# Ganganzeige_nutzen.net
KiCad netlist of a schematic drawn in EAGLE
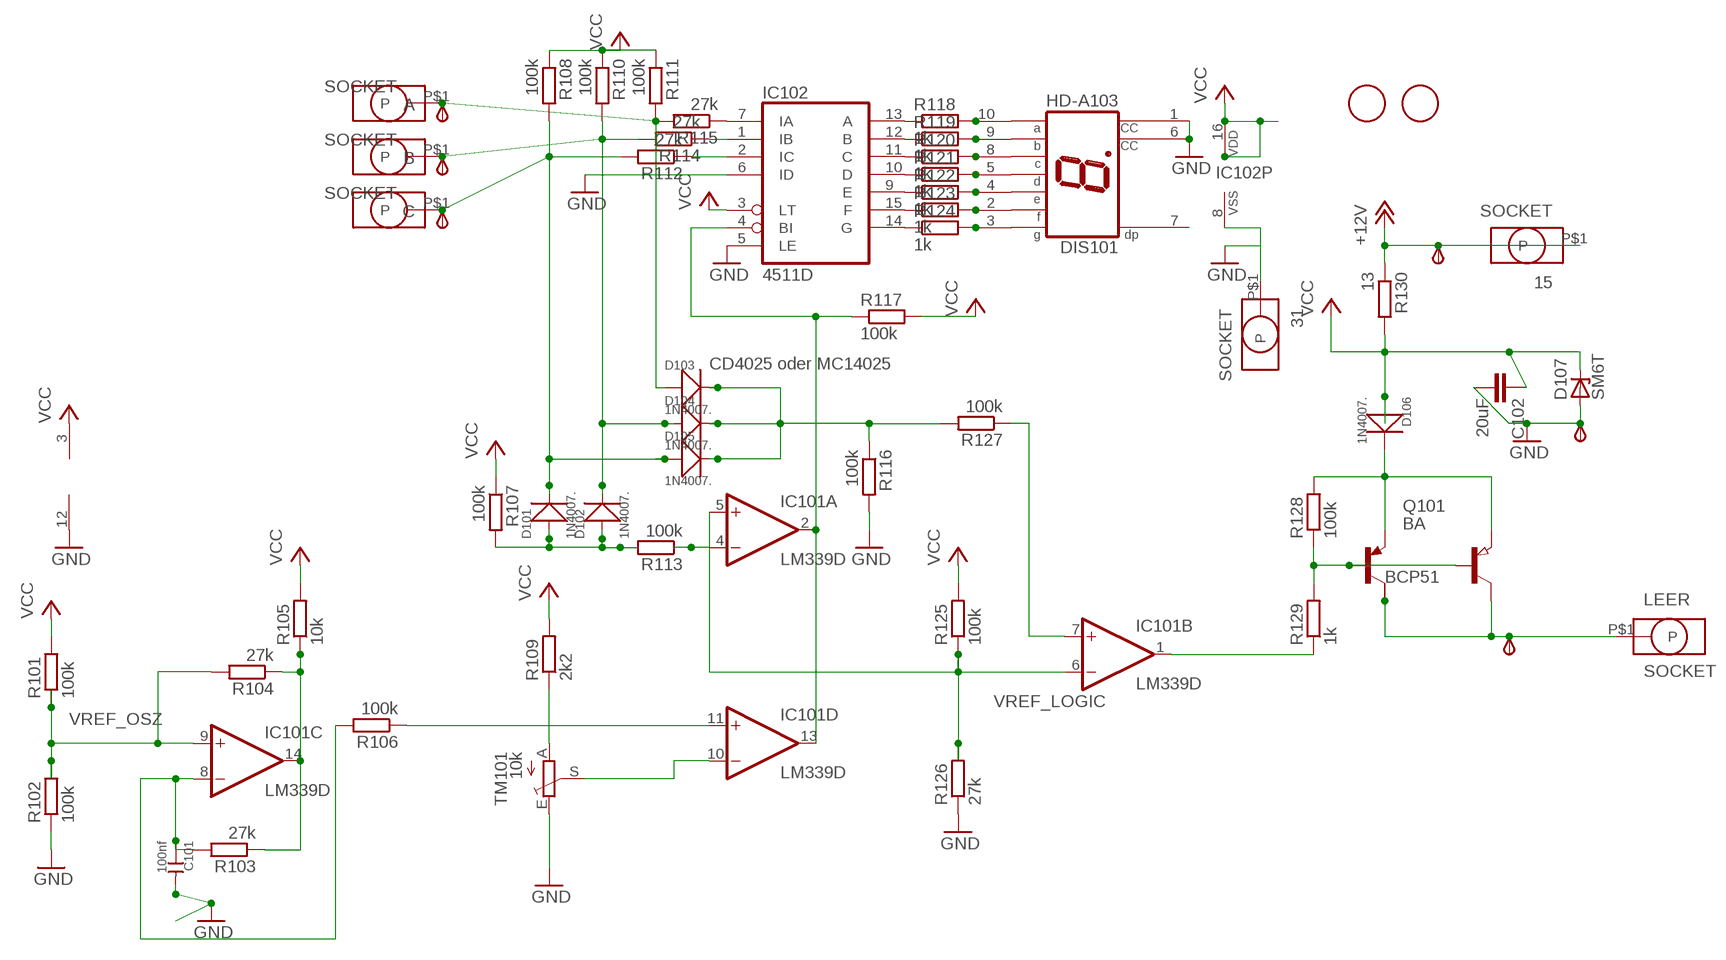
[diagram p0: schematic, sheet 1]
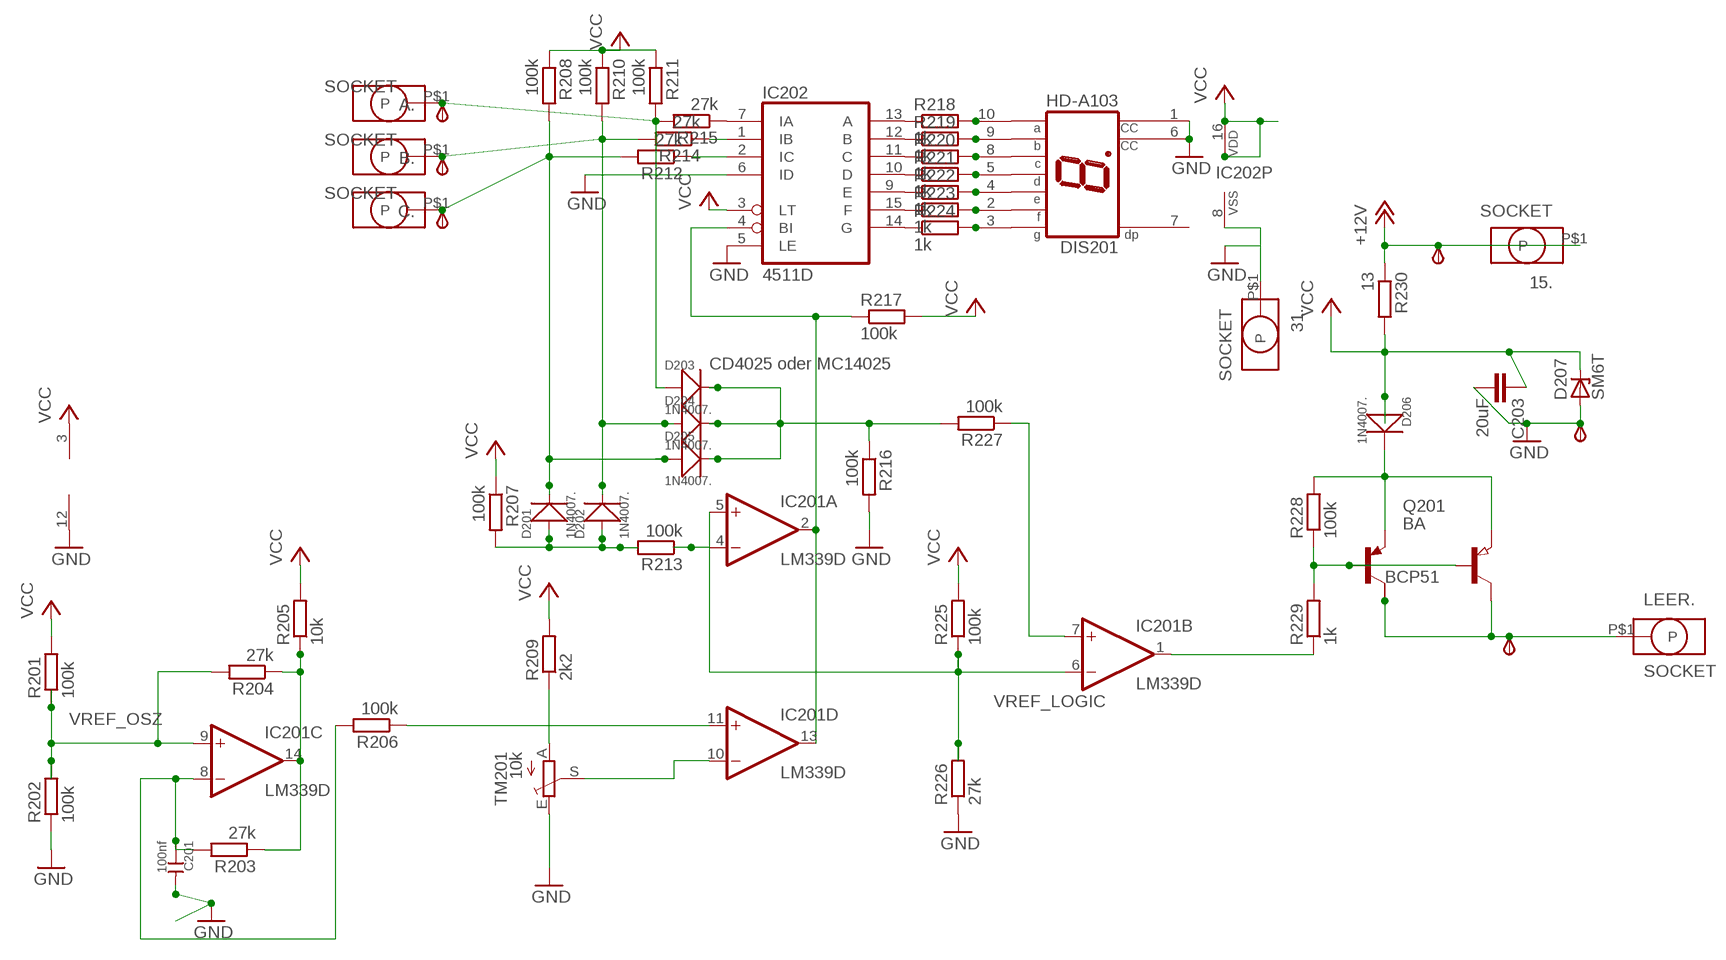
[diagram p1: schematic, sheet 2]
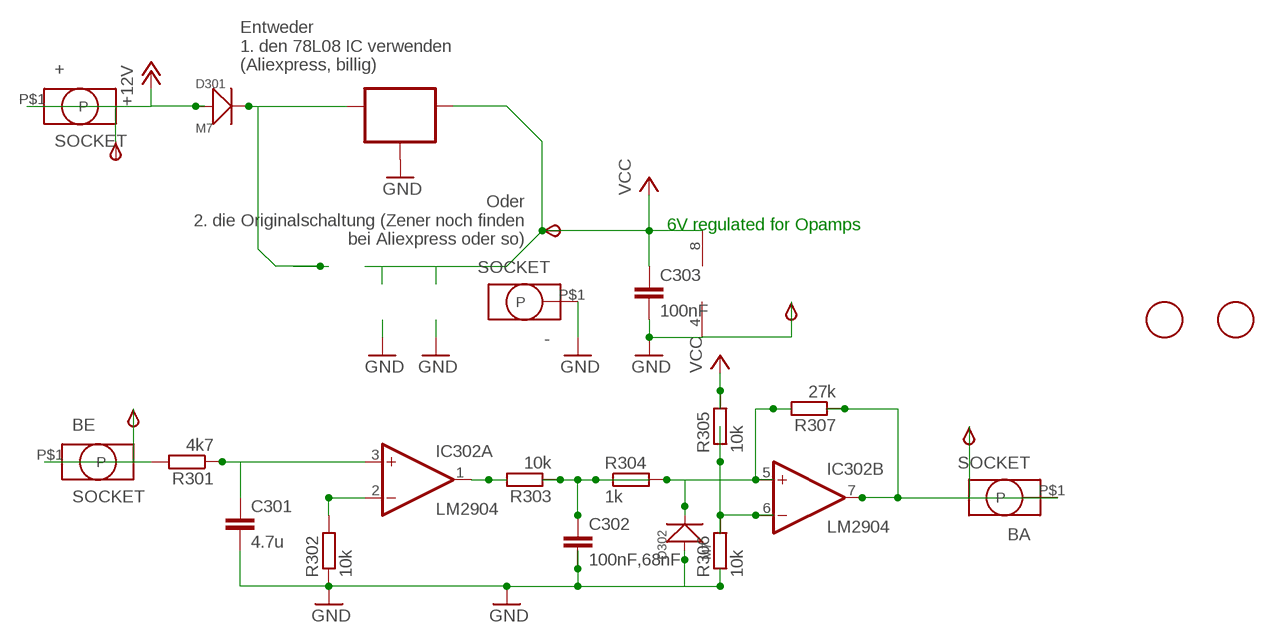
[diagram p2: schematic, sheet 3]
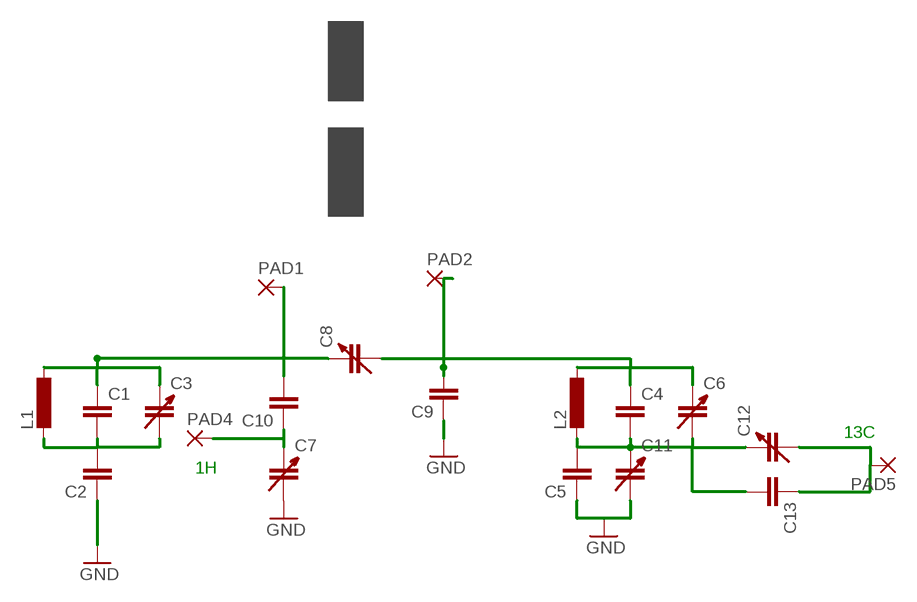
[diagram p3: schematic, sheet 4]

(export (version "E")
  (design (tool "Eeschema 10.0.6"))
  (components
    (comp (ref "C1")
      (value "C-EUC055X055_HIGH_DENSITY")
      (footprint "eagle-import:C055X055_HD")
      (libsource (lib "eagle-import") (part "C-EUC055X055_HIGH_DENSITY"))
    )
    (comp (ref "C2")
      (value "C-EUC055X055_HIGH_DENSITY")
      (footprint "eagle-import:C055X055_HD")
      (libsource (lib "eagle-import") (part "C-EUC055X055_HIGH_DENSITY"))
    )
    (comp (ref "C3")
      (value "CTRIM-EUVOLTRONICS_JZ_SERIES")
      (footprint "eagle-import:VOLTRONICS_JZ")
      (libsource (lib "eagle-import") (part "CTRIM-EUVOLTRONICS_JZ_SERIES"))
    )
    (comp (ref "C4")
      (value "C-EUC055X055_HIGH_DENSITY")
      (footprint "eagle-import:C055X055_HD")
      (libsource (lib "eagle-import") (part "C-EUC055X055_HIGH_DENSITY"))
    )
    (comp (ref "C5")
      (value "C-EUC055X055_HIGH_DENSITY")
      (footprint "eagle-import:C055X055_HD")
      (libsource (lib "eagle-import") (part "C-EUC055X055_HIGH_DENSITY"))
    )
    (comp (ref "C6")
      (value "CTRIM-EUVOLTRONICS_JZ_SERIES")
      (footprint "eagle-import:VOLTRONICS_JZ")
      (libsource (lib "eagle-import") (part "CTRIM-EUVOLTRONICS_JZ_SERIES"))
    )
    (comp (ref "C7")
      (value "CTRIM-EUVOLTRONICS_JZ_SERIES")
      (footprint "eagle-import:VOLTRONICS_JZ")
      (libsource (lib "eagle-import") (part "CTRIM-EUVOLTRONICS_JZ_SERIES"))
    )
    (comp (ref "C8")
      (value "CTRIM-EUVOLTRONICS_JZ_SERIES")
      (footprint "eagle-import:VOLTRONICS_JZ")
      (libsource (lib "eagle-import") (part "CTRIM-EUVOLTRONICS_JZ_SERIES"))
    )
    (comp (ref "C9")
      (value "C-EUC055X055_HIGH_DENSITY")
      (footprint "eagle-import:C055X055_HD")
      (libsource (lib "eagle-import") (part "C-EUC055X055_HIGH_DENSITY"))
    )
    (comp (ref "C10")
      (value "C-EUC055X055_HIGH_DENSITY")
      (footprint "eagle-import:C055X055_HD")
      (libsource (lib "eagle-import") (part "C-EUC055X055_HIGH_DENSITY"))
    )
    (comp (ref "C11")
      (value "CTRIM-EUVOLTRONICS_JZ_SERIES")
      (footprint "eagle-import:VOLTRONICS_JZ")
      (libsource (lib "eagle-import") (part "CTRIM-EUVOLTRONICS_JZ_SERIES"))
    )
    (comp (ref "C12")
      (value "CTRIM-EUVOLTRONICS_JZ_SERIES")
      (footprint "eagle-import:VOLTRONICS_JZ")
      (libsource (lib "eagle-import") (part "CTRIM-EUVOLTRONICS_JZ_SERIES"))
    )
    (comp (ref "C13")
      (value "C-EUC055X055_HIGH_DENSITY")
      (footprint "eagle-import:C055X055_HD")
      (libsource (lib "eagle-import") (part "C-EUC055X055_HIGH_DENSITY"))
    )
    (comp (ref "L1")
      (value "L-EU6WDG_0.5MM_SELFWOUND_COIL")
      (footprint "eagle-import:6WDG_0.5MM")
      (libsource (lib "eagle-import") (part "L-EU6WDG_0.5MM_SELFWOUND_COIL"))
    )
    (comp (ref "L2")
      (value "L-EU6WDG_0.5MM_SELFWOUND_COIL")
      (footprint "eagle-import:6WDG_0.5MM")
      (libsource (lib "eagle-import") (part "L-EU6WDG_0.5MM_SELFWOUND_COIL"))
    )
    (comp (ref "PAD1")
      (value "SMD2")
      (footprint "eagle-import:SMD1,27-2,54")
      (libsource (lib "eagle-import") (part "SMD2"))
    )
    (comp (ref "PAD2")
      (value "SMD2")
      (footprint "eagle-import:SMD1,27-2,54")
      (libsource (lib "eagle-import") (part "SMD2"))
    )
    (comp (ref "PAD4")
      (value "1,6/0,9")
      (footprint "eagle-import:1,6_0,9")
      (libsource (lib "eagle-import") (part "1,6/0,9"))
    )
    (comp (ref "PAD5")
      (value "1,6/0,9")
      (footprint "eagle-import:1,6_0,9")
      (libsource (lib "eagle-import") (part "1,6/0,9"))
    )
    (comp (ref "15")
      (value "SOCKET")
      (footprint "eagle-import:ID2.5MM")
      (libsource (lib "eagle-import") (part "SOCKET"))
    )
    (comp (ref "15_")
      (value "TPSB2.0")
      (footprint "eagle-import:B2.0")
      (libsource (lib "eagle-import") (part "TPSB2.0"))
    )
    (comp (ref "31")
      (value "SOCKET")
      (footprint "eagle-import:ID2.5MM")
      (libsource (lib "eagle-import") (part "SOCKET"))
    )
    (comp (ref "A")
      (value "SOCKET")
      (footprint "eagle-import:ID2.5MM")
      (libsource (lib "eagle-import") (part "SOCKET"))
    )
    (comp (ref "A_")
      (value "TPSB2.0")
      (footprint "eagle-import:B2.0")
      (libsource (lib "eagle-import") (part "TPSB2.0"))
    )
    (comp (ref "B")
      (value "SOCKET")
      (footprint "eagle-import:ID2.5MM")
      (libsource (lib "eagle-import") (part "SOCKET"))
    )
    (comp (ref "B_")
      (value "TPSB2.0")
      (footprint "eagle-import:B2.0")
      (libsource (lib "eagle-import") (part "TPSB2.0"))
    )
    (comp (ref "C")
      (value "SOCKET")
      (footprint "eagle-import:ID2.5MM")
      (libsource (lib "eagle-import") (part "SOCKET"))
    )
    (comp (ref "C101")
      (value "100nf")
      (footprint "eagle-import:C0805")
      (fields (field (name "MPN") "CC0805KRX7R9BB104"))
      (libsource (lib "eagle-import") (part "CERAMIC-100NF-50V-10%-X7R(0805)"))
    )
    (comp (ref "C102")
      (value "20uF")
      (footprint "eagle-import:C1206K")
      (libsource (lib "eagle-import") (part "rcl_C-EUC1206K"))
    )
    (comp (ref "C_")
      (value "TPSB2.0")
      (footprint "eagle-import:B2.0")
      (libsource (lib "eagle-import") (part "TPSB2.0"))
    )
    (comp (ref "D101")
      (value "1N4007.")
      (footprint "eagle-import:DO-214AC")
      (fields (field (name "MPN") "1N4007"))
      (libsource (lib "eagle-import") (part "DIODE-GEN-PURPOSE-1KV-1A(DO-214AC)"))
    )
    (comp (ref "D102")
      (value "1N4007.")
      (footprint "eagle-import:DO-214AC")
      (fields (field (name "MPN") "1N4007"))
      (libsource (lib "eagle-import") (part "DIODE-GEN-PURPOSE-1KV-1A(DO-214AC)"))
    )
    (comp (ref "D103")
      (value "1N4007.")
      (footprint "eagle-import:DO-214AC")
      (fields (field (name "MPN") "1N4007"))
      (libsource (lib "eagle-import") (part "DIODE-GEN-PURPOSE-1KV-1A(DO-214AC)"))
    )
    (comp (ref "D104")
      (value "1N4007.")
      (footprint "eagle-import:DO-214AC")
      (fields (field (name "MPN") "1N4007"))
      (libsource (lib "eagle-import") (part "DIODE-GEN-PURPOSE-1KV-1A(DO-214AC)"))
    )
    (comp (ref "D105")
      (value "1N4007.")
      (footprint "eagle-import:DO-214AC")
      (fields (field (name "MPN") "1N4007"))
      (libsource (lib "eagle-import") (part "DIODE-GEN-PURPOSE-1KV-1A(DO-214AC)"))
    )
    (comp (ref "D106")
      (value "1N4007.")
      (footprint "eagle-import:DO-214AC")
      (fields (field (name "MPN") "1N4007"))
      (libsource (lib "eagle-import") (part "DIODE-GEN-PURPOSE-1KV-1A(DO-214AC)"))
    )
    (comp (ref "D107")
      (value "SM6T")
      (footprint "eagle-import:DO214AA")
      (libsource (lib "eagle-import") (part "SM6T"))
    )
    (comp (ref "DIS101")
      (value "HD-A103")
      (footprint "eagle-import:HDSP-A")
      (libsource (lib "eagle-import") (part "HD-A103"))
    )
    (comp (ref "FID101")
      (value "FIDUCIAL")
      (footprint "eagle-import:FIDUCIAL_1MM")
      (libsource (lib "eagle-import") (part "FIDUCIAL"))
    )
    (comp (ref "FID102")
      (value "FIDUCIAL")
      (footprint "eagle-import:FIDUCIAL_1MM")
      (libsource (lib "eagle-import") (part "FIDUCIAL"))
    )
    (comp (ref "GND_")
      (value "TPSB2.0")
      (footprint "eagle-import:B2.0")
      (libsource (lib "eagle-import") (part "TPSB2.0"))
    )
    (comp (ref "IC101")
      (value "LM339D")
      (footprint "eagle-import:SO14")
      (libsource (lib "eagle-import") (part "LM339D"))
    )
    (comp (ref "IC102")
      (value "4511D")
      (footprint "eagle-import:SO16")
      (libsource (lib "eagle-import") (part "4511D"))
    )
    (comp (ref "LEER")
      (value "SOCKET")
      (footprint "eagle-import:ID2.5MM")
      (libsource (lib "eagle-import") (part "SOCKET"))
    )
    (comp (ref "LEER_")
      (value "TPSB2.0")
      (footprint "eagle-import:B2.0")
      (libsource (lib "eagle-import") (part "TPSB2.0"))
    )
    (comp (ref "Q101")
      (value "BA")
      (footprint "eagle-import:SOT89")
      (libsource (lib "eagle-import") (part "PNP-TRANSISTOR_SOT89"))
    )
    (comp (ref "R101")
      (value "100k")
      (footprint "eagle-import:R0805")
      (libsource (lib "eagle-import") (part "R-EU_R0805"))
    )
    (comp (ref "R102")
      (value "100k")
      (footprint "eagle-import:R0805")
      (libsource (lib "eagle-import") (part "R-EU_R0805"))
    )
    (comp (ref "R103")
      (value "27k")
      (footprint "eagle-import:R0805")
      (libsource (lib "eagle-import") (part "R-EU_R0805"))
    )
    (comp (ref "R104")
      (value "27k")
      (footprint "eagle-import:R0805")
      (libsource (lib "eagle-import") (part "R-EU_R0805"))
    )
    (comp (ref "R105")
      (value "10k")
      (footprint "eagle-import:R0805")
      (libsource (lib "eagle-import") (part "R-EU_R0805"))
    )
    (comp (ref "R106")
      (value "100k")
      (footprint "eagle-import:R0805")
      (libsource (lib "eagle-import") (part "R-EU_R0805"))
    )
    (comp (ref "R107")
      (value "100k")
      (footprint "eagle-import:R0805")
      (libsource (lib "eagle-import") (part "R-EU_R0805"))
    )
    (comp (ref "R108")
      (value "100k")
      (footprint "eagle-import:R0805")
      (libsource (lib "eagle-import") (part "R-EU_R0805"))
    )
    (comp (ref "R109")
      (value "2k2")
      (footprint "eagle-import:R0805")
      (libsource (lib "eagle-import") (part "R-EU_R0805"))
    )
    (comp (ref "R110")
      (value "100k")
      (footprint "eagle-import:R0805")
      (libsource (lib "eagle-import") (part "R-EU_R0805"))
    )
    (comp (ref "R111")
      (value "100k")
      (footprint "eagle-import:R0805")
      (libsource (lib "eagle-import") (part "R-EU_R0805"))
    )
    (comp (ref "R112")
      (value "27k")
      (footprint "eagle-import:R0805")
      (libsource (lib "eagle-import") (part "R-EU_R0805"))
    )
    (comp (ref "R113")
      (value "100k")
      (footprint "eagle-import:R0805")
      (libsource (lib "eagle-import") (part "R-EU_R0805"))
    )
    (comp (ref "R114")
      (value "27k")
      (footprint "eagle-import:R0805")
      (libsource (lib "eagle-import") (part "R-EU_R0805"))
    )
    (comp (ref "R115")
      (value "27k")
      (footprint "eagle-import:R0805")
      (libsource (lib "eagle-import") (part "R-EU_R0805"))
    )
    (comp (ref "R116")
      (value "100k")
      (footprint "eagle-import:R0805")
      (libsource (lib "eagle-import") (part "R-EU_R0805"))
    )
    (comp (ref "R117")
      (value "100k")
      (footprint "eagle-import:R0805")
      (libsource (lib "eagle-import") (part "R-EU_R0805"))
    )
    (comp (ref "R118")
      (value "1k")
      (footprint "eagle-import:R0805")
      (libsource (lib "eagle-import") (part "R-EU_R0805"))
    )
    (comp (ref "R119")
      (value "1k")
      (footprint "eagle-import:R0805")
      (libsource (lib "eagle-import") (part "R-EU_R0805"))
    )
    (comp (ref "R120")
      (value "1k")
      (footprint "eagle-import:R0805")
      (libsource (lib "eagle-import") (part "R-EU_R0805"))
    )
    (comp (ref "R121")
      (value "1k")
      (footprint "eagle-import:R0805")
      (libsource (lib "eagle-import") (part "R-EU_R0805"))
    )
    (comp (ref "R122")
      (value "1k")
      (footprint "eagle-import:R0805")
      (libsource (lib "eagle-import") (part "R-EU_R0805"))
    )
    (comp (ref "R123")
      (value "1k")
      (footprint "eagle-import:R0805")
      (libsource (lib "eagle-import") (part "R-EU_R0805"))
    )
    (comp (ref "R124")
      (value "1k")
      (footprint "eagle-import:R0805")
      (libsource (lib "eagle-import") (part "R-EU_R0805"))
    )
    (comp (ref "R125")
      (value "100k")
      (footprint "eagle-import:R0805")
      (libsource (lib "eagle-import") (part "R-EU_R0805"))
    )
    (comp (ref "R126")
      (value "27k")
      (footprint "eagle-import:R0805")
      (libsource (lib "eagle-import") (part "R-EU_R0805"))
    )
    (comp (ref "R127")
      (value "100k")
      (footprint "eagle-import:R0805")
      (libsource (lib "eagle-import") (part "R-EU_R0805"))
    )
    (comp (ref "R128")
      (value "100k")
      (footprint "eagle-import:R0805")
      (libsource (lib "eagle-import") (part "R-EU_R0805"))
    )
    (comp (ref "R129")
      (value "1k")
      (footprint "eagle-import:R0805")
      (libsource (lib "eagle-import") (part "R-EU_R0805"))
    )
    (comp (ref "R130")
      (value "13")
      (footprint "eagle-import:R1206")
      (libsource (lib "eagle-import") (part "R-EU_R1206"))
    )
    (comp (ref "T")
      (value "BCP53T1")
      (footprint "eagle-import:SOT223")
      (fields (field (name "T") "BCP51"))
      (libsource (lib "eagle-import") (part "BCP53T1"))
    )
    (comp (ref "TM101")
      (value "10k")
      (footprint "eagle-import:S63X")
      (libsource (lib "eagle-import") (part "TRIM_EU-S63X"))
    )
    (comp (ref "+")
      (value "SOCKET")
      (footprint "eagle-import:ID2.5MM")
      (libsource (lib "eagle-import") (part "SOCKET"))
    )
    (comp (ref "+12V")
      (value "TPSB2.0")
      (footprint "eagle-import:B2.0")
      (libsource (lib "eagle-import") (part "TPSB2.0"))
    )
    (comp (ref "-")
      (value "SOCKET")
      (footprint "eagle-import:ID2.5MM")
      (libsource (lib "eagle-import") (part "SOCKET"))
    )
    (comp (ref "6V")
      (value "TPSB2.0")
      (footprint "eagle-import:B2.0")
      (libsource (lib "eagle-import") (part "TPSB2.0"))
    )
    (comp (ref "AUS")
      (value "TPSB2.0")
      (footprint "eagle-import:B2.0")
      (libsource (lib "eagle-import") (part "TPSB2.0"))
    )
    (comp (ref "BA")
      (value "SOCKET")
      (footprint "eagle-import:ID2.5MM")
      (libsource (lib "eagle-import") (part "SOCKET"))
    )
    (comp (ref "BE")
      (value "SOCKET")
      (footprint "eagle-import:ID2.5MM")
      (libsource (lib "eagle-import") (part "SOCKET"))
    )
    (comp (ref "C301")
      (value "4.7u")
      (footprint "eagle-import:C0805K")
      (libsource (lib "eagle-import") (part "rcl_C-EUC0805K"))
    )
    (comp (ref "C302")
      (value "100nF,68nF")
      (footprint "eagle-import:C0805K")
      (libsource (lib "eagle-import") (part "rcl_C-EUC0805K"))
    )
    (comp (ref "C303")
      (value "100nF")
      (footprint "eagle-import:C0805K")
      (libsource (lib "eagle-import") (part "rcl_C-EUC0805K"))
    )
    (comp (ref "D301")
      (value "M7")
      (footprint "eagle-import:DO-214AC")
      (fields (field (name "MPN") "1N4007"))
      (libsource (lib "eagle-import") (part "DIODE-GEN-PURPOSE-1KV-1A(DO-214AC)"))
    )
    (comp (ref "D302")
      (value "M7")
      (footprint "eagle-import:DO-214AC")
      (fields (field (name "MPN") "1N4007"))
      (libsource (lib "eagle-import") (part "DIODE-GEN-PURPOSE-1KV-1A(DO-214AC)"))
    )
    (comp (ref "EIN")
      (value "TPSB2.0")
      (footprint "eagle-import:B2.0")
      (libsource (lib "eagle-import") (part "TPSB2.0"))
    )
    (comp (ref "FID301")
      (value "FIDUCIAL")
      (footprint "eagle-import:FIDUCIAL_1MM")
      (libsource (lib "eagle-import") (part "FIDUCIAL"))
    )
    (comp (ref "FID302")
      (value "FIDUCIAL")
      (footprint "eagle-import:FIDUCIAL_1MM")
      (libsource (lib "eagle-import") (part "FIDUCIAL"))
    )
    (comp (ref "GND")
      (value "TPSB2.0")
      (footprint "eagle-import:B2.0")
      (libsource (lib "eagle-import") (part "TPSB2.0"))
    )
    (comp (ref "IC301")
      (value "5V/6V oder 8V Regler")
      (footprint "eagle-import:SOT89_ROUND")
      (libsource (lib "eagle-import") (part "78LXXSOT89_ROUND"))
    )
    (comp (ref "IC302")
      (value "LM2904")
      (footprint "eagle-import:SO08")
      (libsource (lib "eagle-import") (part "LM358D"))
    )
    (comp (ref "R301")
      (value "4k7")
      (footprint "eagle-import:R0805")
      (libsource (lib "eagle-import") (part "R-EU_R0805"))
    )
    (comp (ref "R302")
      (value "10k")
      (footprint "eagle-import:R0805")
      (libsource (lib "eagle-import") (part "R-EU_R0805"))
    )
    (comp (ref "R303")
      (value "10k")
      (footprint "eagle-import:R0805")
      (libsource (lib "eagle-import") (part "R-EU_R0805"))
    )
    (comp (ref "R304")
      (value "1k")
      (footprint "eagle-import:R0805")
      (libsource (lib "eagle-import") (part "R-EU_R0805"))
    )
    (comp (ref "R305")
      (value "10k")
      (footprint "eagle-import:R0805")
      (libsource (lib "eagle-import") (part "R-EU_R0805"))
    )
    (comp (ref "R306")
      (value "10k")
      (footprint "eagle-import:R0805")
      (libsource (lib "eagle-import") (part "R-EU_R0805"))
    )
    (comp (ref "R307")
      (value "27k")
      (footprint "eagle-import:R0805")
      (libsource (lib "eagle-import") (part "R-EU_R0805"))
    )
    (comp (ref "15.")
      (value "SOCKET")
      (footprint "eagle-import:ID2.5MM")
      (libsource (lib "eagle-import") (part "SOCKET"))
    )
    (comp (ref "15_201")
      (value "TPSB2.0")
      (footprint "eagle-import:B2.0")
      (libsource (lib "eagle-import") (part "TPSB2.0"))
    )
    (comp (ref "31.")
      (value "SOCKET")
      (footprint "eagle-import:ID2.5MM")
      (libsource (lib "eagle-import") (part "SOCKET"))
    )
    (comp (ref "A.")
      (value "SOCKET")
      (footprint "eagle-import:ID2.5MM")
      (libsource (lib "eagle-import") (part "SOCKET"))
    )
    (comp (ref "A_201")
      (value "TPSB2.0")
      (footprint "eagle-import:B2.0")
      (libsource (lib "eagle-import") (part "TPSB2.0"))
    )
    (comp (ref "B.")
      (value "SOCKET")
      (footprint "eagle-import:ID2.5MM")
      (libsource (lib "eagle-import") (part "SOCKET"))
    )
    (comp (ref "B_201")
      (value "TPSB2.0")
      (footprint "eagle-import:B2.0")
      (libsource (lib "eagle-import") (part "TPSB2.0"))
    )
    (comp (ref "C.")
      (value "SOCKET")
      (footprint "eagle-import:ID2.5MM")
      (libsource (lib "eagle-import") (part "SOCKET"))
    )
    (comp (ref "C201")
      (value "100nf")
      (footprint "eagle-import:C0805")
      (fields (field (name "MPN") "CC0805KRX7R9BB104"))
      (libsource (lib "eagle-import") (part "CERAMIC-100NF-50V-10%-X7R(0805)"))
    )
    (comp (ref "C203")
      (value "20uF")
      (footprint "eagle-import:C1206K")
      (libsource (lib "eagle-import") (part "rcl_C-EUC1206K"))
    )
    (comp (ref "C_201")
      (value "TPSB2.0")
      (footprint "eagle-import:B2.0")
      (libsource (lib "eagle-import") (part "TPSB2.0"))
    )
    (comp (ref "D201")
      (value "1N4007.")
      (footprint "eagle-import:DO-214AC")
      (fields (field (name "MPN") "1N4007"))
      (libsource (lib "eagle-import") (part "DIODE-GEN-PURPOSE-1KV-1A(DO-214AC)"))
    )
    (comp (ref "D202")
      (value "1N4007.")
      (footprint "eagle-import:DO-214AC")
      (fields (field (name "MPN") "1N4007"))
      (libsource (lib "eagle-import") (part "DIODE-GEN-PURPOSE-1KV-1A(DO-214AC)"))
    )
    (comp (ref "D203")
      (value "1N4007.")
      (footprint "eagle-import:DO-214AC")
      (fields (field (name "MPN") "1N4007"))
      (libsource (lib "eagle-import") (part "DIODE-GEN-PURPOSE-1KV-1A(DO-214AC)"))
    )
    (comp (ref "D204")
      (value "1N4007.")
      (footprint "eagle-import:DO-214AC")
      (fields (field (name "MPN") "1N4007"))
      (libsource (lib "eagle-import") (part "DIODE-GEN-PURPOSE-1KV-1A(DO-214AC)"))
    )
    (comp (ref "D205")
      (value "1N4007.")
      (footprint "eagle-import:DO-214AC")
      (fields (field (name "MPN") "1N4007"))
      (libsource (lib "eagle-import") (part "DIODE-GEN-PURPOSE-1KV-1A(DO-214AC)"))
    )
    (comp (ref "D206")
      (value "1N4007.")
      (footprint "eagle-import:DO-214AC")
      (fields (field (name "MPN") "1N4007"))
      (libsource (lib "eagle-import") (part "DIODE-GEN-PURPOSE-1KV-1A(DO-214AC)"))
    )
    (comp (ref "D207")
      (value "SM6T")
      (footprint "eagle-import:DO214AA")
      (libsource (lib "eagle-import") (part "SM6T"))
    )
    (comp (ref "DIS201")
      (value "HD-A103")
      (footprint "eagle-import:HDSP-A")
      (libsource (lib "eagle-import") (part "HD-A103"))
    )
    (comp (ref "GND_201")
      (value "TPSB2.0")
      (footprint "eagle-import:B2.0")
      (libsource (lib "eagle-import") (part "TPSB2.0"))
    )
    (comp (ref "IC201")
      (value "LM339D")
      (footprint "eagle-import:SO14")
      (libsource (lib "eagle-import") (part "LM339D"))
    )
    (comp (ref "IC202")
      (value "4511D")
      (footprint "eagle-import:SO16")
      (libsource (lib "eagle-import") (part "4511D"))
    )
    (comp (ref "LEER.")
      (value "SOCKET")
      (footprint "eagle-import:ID2.5MM")
      (libsource (lib "eagle-import") (part "SOCKET"))
    )
    (comp (ref "LEER_201")
      (value "TPSB2.0")
      (footprint "eagle-import:B2.0")
      (libsource (lib "eagle-import") (part "TPSB2.0"))
    )
    (comp (ref "Q201")
      (value "BA")
      (footprint "eagle-import:SOT89")
      (libsource (lib "eagle-import") (part "PNP-TRANSISTOR_SOT89"))
    )
    (comp (ref "R201")
      (value "100k")
      (footprint "eagle-import:R0805")
      (libsource (lib "eagle-import") (part "R-EU_R0805"))
    )
    (comp (ref "R202")
      (value "100k")
      (footprint "eagle-import:R0805")
      (libsource (lib "eagle-import") (part "R-EU_R0805"))
    )
    (comp (ref "R203")
      (value "27k")
      (footprint "eagle-import:R0805")
      (libsource (lib "eagle-import") (part "R-EU_R0805"))
    )
    (comp (ref "R204")
      (value "27k")
      (footprint "eagle-import:R0805")
      (libsource (lib "eagle-import") (part "R-EU_R0805"))
    )
    (comp (ref "R205")
      (value "10k")
      (footprint "eagle-import:R0805")
      (libsource (lib "eagle-import") (part "R-EU_R0805"))
    )
    (comp (ref "R206")
      (value "100k")
      (footprint "eagle-import:R0805")
      (libsource (lib "eagle-import") (part "R-EU_R0805"))
    )
    (comp (ref "R207")
      (value "100k")
      (footprint "eagle-import:R0805")
      (libsource (lib "eagle-import") (part "R-EU_R0805"))
    )
    (comp (ref "R208")
      (value "100k")
      (footprint "eagle-import:R0805")
      (libsource (lib "eagle-import") (part "R-EU_R0805"))
    )
    (comp (ref "R209")
      (value "2k2")
      (footprint "eagle-import:R0805")
      (libsource (lib "eagle-import") (part "R-EU_R0805"))
    )
    (comp (ref "R210")
      (value "100k")
      (footprint "eagle-import:R0805")
      (libsource (lib "eagle-import") (part "R-EU_R0805"))
    )
    (comp (ref "R211")
      (value "100k")
      (footprint "eagle-import:R0805")
      (libsource (lib "eagle-import") (part "R-EU_R0805"))
    )
    (comp (ref "R212")
      (value "27k")
      (footprint "eagle-import:R0805")
      (libsource (lib "eagle-import") (part "R-EU_R0805"))
    )
    (comp (ref "R213")
      (value "100k")
      (footprint "eagle-import:R0805")
      (libsource (lib "eagle-import") (part "R-EU_R0805"))
    )
    (comp (ref "R214")
      (value "27k")
      (footprint "eagle-import:R0805")
      (libsource (lib "eagle-import") (part "R-EU_R0805"))
    )
    (comp (ref "R215")
      (value "27k")
      (footprint "eagle-import:R0805")
      (libsource (lib "eagle-import") (part "R-EU_R0805"))
    )
    (comp (ref "R216")
      (value "100k")
      (footprint "eagle-import:R0805")
      (libsource (lib "eagle-import") (part "R-EU_R0805"))
    )
    (comp (ref "R217")
      (value "100k")
      (footprint "eagle-import:R0805")
      (libsource (lib "eagle-import") (part "R-EU_R0805"))
    )
    (comp (ref "R218")
      (value "1k")
      (footprint "eagle-import:R0805")
      (libsource (lib "eagle-import") (part "R-EU_R0805"))
    )
    (comp (ref "R219")
      (value "1k")
      (footprint "eagle-import:R0805")
      (libsource (lib "eagle-import") (part "R-EU_R0805"))
    )
    (comp (ref "R220")
      (value "1k")
      (footprint "eagle-import:R0805")
      (libsource (lib "eagle-import") (part "R-EU_R0805"))
    )
    (comp (ref "R221")
      (value "1k")
      (footprint "eagle-import:R0805")
      (libsource (lib "eagle-import") (part "R-EU_R0805"))
    )
    (comp (ref "R222")
      (value "1k")
      (footprint "eagle-import:R0805")
      (libsource (lib "eagle-import") (part "R-EU_R0805"))
    )
    (comp (ref "R223")
      (value "1k")
      (footprint "eagle-import:R0805")
      (libsource (lib "eagle-import") (part "R-EU_R0805"))
    )
    (comp (ref "R224")
      (value "1k")
      (footprint "eagle-import:R0805")
      (libsource (lib "eagle-import") (part "R-EU_R0805"))
    )
    (comp (ref "R225")
      (value "100k")
      (footprint "eagle-import:R0805")
      (libsource (lib "eagle-import") (part "R-EU_R0805"))
    )
    (comp (ref "R226")
      (value "27k")
      (footprint "eagle-import:R0805")
      (libsource (lib "eagle-import") (part "R-EU_R0805"))
    )
    (comp (ref "R227")
      (value "100k")
      (footprint "eagle-import:R0805")
      (libsource (lib "eagle-import") (part "R-EU_R0805"))
    )
    (comp (ref "R228")
      (value "100k")
      (footprint "eagle-import:R0805")
      (libsource (lib "eagle-import") (part "R-EU_R0805"))
    )
    (comp (ref "R229")
      (value "1k")
      (footprint "eagle-import:R0805")
      (libsource (lib "eagle-import") (part "R-EU_R0805"))
    )
    (comp (ref "R230")
      (value "13")
      (footprint "eagle-import:R1206")
      (libsource (lib "eagle-import") (part "R-EU_R1206"))
    )
    (comp (ref "T201")
      (value "BCP53T1")
      (footprint "eagle-import:SOT223")
      (fields (field (name "T") "BCP51"))
      (libsource (lib "eagle-import") (part "BCP53T1"))
    )
    (comp (ref "TM201")
      (value "10k")
      (footprint "eagle-import:S63X")
      (libsource (lib "eagle-import") (part "TRIM_EU-S63X"))
    )
  )
  (nets
    (net (code "1") (name "+12V") (class "Default")
      (node (ref "+") (pin "P$1") (pinfunction "P_P$1") (pintype "bidirectional"))
      (node (ref "+12V") (pin "TP") (pinfunction "PP_TP") (pintype "input"))
      (node (ref "15") (pin "P$1") (pinfunction "P_P$1") (pintype "bidirectional"))
      (node (ref "15.") (pin "P$1") (pinfunction "P_P$1") (pintype "bidirectional"))
      (node (ref "15_") (pin "TP") (pinfunction "PP_TP") (pintype "input"))
      (node (ref "15_201") (pin "TP") (pinfunction "PP_TP") (pintype "input"))
      (node (ref "D301") (pin "1") (pinfunction "+_1") (pintype "passive"))
      (node (ref "R130") (pin "1") (pinfunction "1_1") (pintype "passive"))
      (node (ref "R230") (pin "1") (pinfunction "1_1") (pintype "passive"))
    )
    (net (code "2") (name "GND") (class "Default")
      (node (ref "-") (pin "P$1") (pinfunction "P_P$1") (pintype "bidirectional"))
      (node (ref "31") (pin "P$1") (pinfunction "P_P$1") (pintype "bidirectional"))
      (node (ref "31.") (pin "P$1") (pinfunction "P_P$1") (pintype "bidirectional"))
      (node (ref "C101") (pin "2") (pinfunction "2_2") (pintype "passive"))
      (node (ref "C102") (pin "2") (pinfunction "2_2") (pintype "passive"))
      (node (ref "C11") (pin "2") (pinfunction "2_2") (pintype "passive"))
      (node (ref "C2") (pin "1") (pinfunction "1_1") (pintype "passive"))
      (node (ref "C201") (pin "2") (pinfunction "2_2") (pintype "passive"))
      (node (ref "C203") (pin "2") (pinfunction "2_2") (pintype "passive"))
      (node (ref "C301") (pin "2") (pinfunction "2_2") (pintype "passive"))
      (node (ref "C302") (pin "2") (pinfunction "2_2") (pintype "passive"))
      (node (ref "C303") (pin "2") (pinfunction "2_2") (pintype "passive"))
      (node (ref "C5") (pin "1") (pinfunction "1_1") (pintype "passive"))
      (node (ref "C7") (pin "2") (pinfunction "2_2") (pintype "passive"))
      (node (ref "C9") (pin "1") (pinfunction "1_1") (pintype "passive"))
      (node (ref "D107") (pin "A") (pinfunction "A_A") (pintype "passive"))
      (node (ref "D207") (pin "A") (pinfunction "A_A") (pintype "passive"))
      (node (ref "D302") (pin "1") (pinfunction "+_1") (pintype "passive"))
      (node (ref "DIS101") (pin "1") (pinfunction "CC_1") (pintype "passive"))
      (node (ref "DIS101") (pin "6") (pinfunction "CC_6") (pintype "passive"))
      (node (ref "DIS201") (pin "1") (pinfunction "CC_1") (pintype "passive"))
      (node (ref "DIS201") (pin "6") (pinfunction "CC_6") (pintype "passive"))
      (node (ref "GND") (pin "TP") (pinfunction "PP_TP") (pintype "input"))
      (node (ref "GND_") (pin "TP") (pinfunction "PP_TP") (pintype "input"))
      (node (ref "GND_201") (pin "TP") (pinfunction "PP_TP") (pintype "input"))
      (node (ref "IC101") (pin "12") (pinfunction "GND_12") (pintype "power_in"))
      (node (ref "IC102") (pin "5") (pinfunction "LE_5") (pintype "input"))
      (node (ref "IC102") (pin "6") (pinfunction "ID_6") (pintype "input"))
      (node (ref "IC102") (pin "8") (pinfunction "VSS_8") (pintype "power_in"))
      (node (ref "IC201") (pin "12") (pinfunction "GND_12") (pintype "power_in"))
      (node (ref "IC202") (pin "5") (pinfunction "LE_5") (pintype "input"))
      (node (ref "IC202") (pin "6") (pinfunction "ID_6") (pintype "input"))
      (node (ref "IC202") (pin "8") (pinfunction "VSS_8") (pintype "power_in"))
      (node (ref "IC301") (pin "2") (pinfunction "GND_2") (pintype "input"))
      (node (ref "IC301") (pin "2@1") (pinfunction "GND_2@1") (pintype "input"))
      (node (ref "IC302") (pin "4") (pinfunction "V-_4") (pintype "power_in"))
      (node (ref "R102") (pin "1") (pinfunction "1_1") (pintype "passive"))
      (node (ref "R116") (pin "2") (pinfunction "2_2") (pintype "passive"))
      (node (ref "R126") (pin "1") (pinfunction "1_1") (pintype "passive"))
      (node (ref "R202") (pin "1") (pinfunction "1_1") (pintype "passive"))
      (node (ref "R216") (pin "2") (pinfunction "2_2") (pintype "passive"))
      (node (ref "R226") (pin "1") (pinfunction "1_1") (pintype "passive"))
      (node (ref "R302") (pin "1") (pinfunction "1_1") (pintype "passive"))
      (node (ref "R306") (pin "1") (pinfunction "1_1") (pintype "passive"))
      (node (ref "TM101") (pin "E") (pinfunction "E_E") (pintype "passive"))
      (node (ref "TM201") (pin "E") (pinfunction "E_E") (pintype "passive"))
    )
    (net (code "3") (name "Net-(A-P)") (class "Default")
      (node (ref "A") (pin "P$1") (pinfunction "P_P$1") (pintype "bidirectional"))
      (node (ref "A_") (pin "TP") (pinfunction "PP_TP") (pintype "input"))
      (node (ref "D103") (pin "1") (pinfunction "+_1") (pintype "passive"))
      (node (ref "R111") (pin "2") (pinfunction "2_2") (pintype "passive"))
      (node (ref "R115") (pin "2") (pinfunction "2_2") (pintype "passive"))
    )
    (net (code "4") (name "Net-(A.-P)") (class "Default")
      (node (ref "A.") (pin "P$1") (pinfunction "P_P$1") (pintype "bidirectional"))
      (node (ref "A_201") (pin "TP") (pinfunction "PP_TP") (pintype "input"))
      (node (ref "D203") (pin "1") (pinfunction "+_1") (pintype "passive"))
      (node (ref "R211") (pin "2") (pinfunction "2_2") (pintype "passive"))
      (node (ref "R215") (pin "2") (pinfunction "2_2") (pintype "passive"))
    )
    (net (code "5") (name "Net-(AUS-PP)") (class "Default")
      (node (ref "AUS") (pin "TP") (pinfunction "PP_TP") (pintype "input"))
      (node (ref "BA") (pin "P$1") (pinfunction "P_P$1") (pintype "bidirectional"))
      (node (ref "IC302") (pin "7") (pinfunction "OUT_7") (pintype "output"))
      (node (ref "R307") (pin "1") (pinfunction "1_1") (pintype "passive"))
    )
    (net (code "6") (name "Net-(B-P)") (class "Default")
      (node (ref "B") (pin "P$1") (pinfunction "P_P$1") (pintype "bidirectional"))
      (node (ref "B_") (pin "TP") (pinfunction "PP_TP") (pintype "input"))
      (node (ref "D102") (pin "2") (pinfunction "-_2") (pintype "passive"))
      (node (ref "D104") (pin "1") (pinfunction "+_1") (pintype "passive"))
      (node (ref "R110") (pin "2") (pinfunction "2_2") (pintype "passive"))
      (node (ref "R114") (pin "2") (pinfunction "2_2") (pintype "passive"))
    )
    (net (code "7") (name "Net-(B.-P)") (class "Default")
      (node (ref "B.") (pin "P$1") (pinfunction "P_P$1") (pintype "bidirectional"))
      (node (ref "B_201") (pin "TP") (pinfunction "PP_TP") (pintype "input"))
      (node (ref "D202") (pin "2") (pinfunction "-_2") (pintype "passive"))
      (node (ref "D204") (pin "1") (pinfunction "+_1") (pintype "passive"))
      (node (ref "R210") (pin "2") (pinfunction "2_2") (pintype "passive"))
      (node (ref "R214") (pin "2") (pinfunction "2_2") (pintype "passive"))
    )
    (net (code "8") (name "Net-(BE-P)") (class "Default")
      (node (ref "BE") (pin "P$1") (pinfunction "P_P$1") (pintype "bidirectional"))
      (node (ref "EIN") (pin "TP") (pinfunction "PP_TP") (pintype "input"))
      (node (ref "R301") (pin "2") (pinfunction "2_2") (pintype "passive"))
    )
    (net (code "9") (name "Net-(C-P)") (class "Default")
      (node (ref "C") (pin "P$1") (pinfunction "P_P$1") (pintype "bidirectional"))
      (node (ref "C_") (pin "TP") (pinfunction "PP_TP") (pintype "input"))
      (node (ref "D101") (pin "2") (pinfunction "-_2") (pintype "passive"))
      (node (ref "D105") (pin "1") (pinfunction "+_1") (pintype "passive"))
      (node (ref "R108") (pin "2") (pinfunction "2_2") (pintype "passive"))
      (node (ref "R112") (pin "2") (pinfunction "2_2") (pintype "passive"))
    )
    (net (code "10") (name "Net-(C.-P)") (class "Default")
      (node (ref "C.") (pin "P$1") (pinfunction "P_P$1") (pintype "bidirectional"))
      (node (ref "C_201") (pin "TP") (pinfunction "PP_TP") (pintype "input"))
      (node (ref "D201") (pin "2") (pinfunction "-_2") (pintype "passive"))
      (node (ref "D205") (pin "1") (pinfunction "+_1") (pintype "passive"))
      (node (ref "R208") (pin "2") (pinfunction "2_2") (pintype "passive"))
      (node (ref "R212") (pin "2") (pinfunction "2_2") (pintype "passive"))
    )
    (net (code "11") (name "Net-(C1-Pad2)") (class "Default")
      (node (ref "C1") (pin "2") (pinfunction "2_2") (pintype "passive"))
      (node (ref "C2") (pin "2") (pinfunction "2_2") (pintype "passive"))
      (node (ref "C3") (pin "2") (pinfunction "2_2") (pintype "passive"))
      (node (ref "L1") (pin "2") (pinfunction "2_2") (pintype "passive"))
    )
    (net (code "12") (name "Net-(C11-Pad1)") (class "Default")
      (node (ref "C11") (pin "1") (pinfunction "1_1") (pintype "passive"))
      (node (ref "C12") (pin "1") (pinfunction "1_1") (pintype "passive"))
      (node (ref "C13") (pin "2") (pinfunction "2_2") (pintype "passive"))
      (node (ref "C4") (pin "2") (pinfunction "2_2") (pintype "passive"))
      (node (ref "C5") (pin "2") (pinfunction "2_2") (pintype "passive"))
      (node (ref "C6") (pin "2") (pinfunction "2_2") (pintype "passive"))
      (node (ref "L2") (pin "2") (pinfunction "2_2") (pintype "passive"))
    )
    (net (code "13") (name "Net-(C302-Pad1)") (class "Default")
      (node (ref "C302") (pin "1") (pinfunction "1_1") (pintype "passive"))
      (node (ref "R303") (pin "1") (pinfunction "1_1") (pintype "passive"))
      (node (ref "R304") (pin "1") (pinfunction "1_1") (pintype "passive"))
    )
    (net (code "14") (name "Net-(D101-+)") (class "Default")
      (node (ref "D101") (pin "1") (pinfunction "+_1") (pintype "passive"))
      (node (ref "D102") (pin "1") (pinfunction "+_1") (pintype "passive"))
      (node (ref "R107") (pin "2") (pinfunction "2_2") (pintype "passive"))
      (node (ref "R113") (pin "2") (pinfunction "2_2") (pintype "passive"))
    )
    (net (code "15") (name "Net-(D103--)") (class "Default")
      (node (ref "D103") (pin "2") (pinfunction "-_2") (pintype "passive"))
      (node (ref "D104") (pin "2") (pinfunction "-_2") (pintype "passive"))
      (node (ref "D105") (pin "2") (pinfunction "-_2") (pintype "passive"))
      (node (ref "R116") (pin "1") (pinfunction "1_1") (pintype "passive"))
      (node (ref "R127") (pin "2") (pinfunction "2_2") (pintype "passive"))
    )
    (net (code "16") (name "Net-(D106--)") (class "Default")
      (node (ref "D106") (pin "2") (pinfunction "-_2") (pintype "passive"))
      (node (ref "Q101") (pin "3") (pinfunction "E_3") (pintype "passive"))
      (node (ref "R128") (pin "2") (pinfunction "2_2") (pintype "passive"))
      (node (ref "T") (pin "3") (pinfunction "E_3") (pintype "passive"))
    )
    (net (code "17") (name "Net-(D201-+)") (class "Default")
      (node (ref "D201") (pin "1") (pinfunction "+_1") (pintype "passive"))
      (node (ref "D202") (pin "1") (pinfunction "+_1") (pintype "passive"))
      (node (ref "R207") (pin "2") (pinfunction "2_2") (pintype "passive"))
      (node (ref "R213") (pin "2") (pinfunction "2_2") (pintype "passive"))
    )
    (net (code "18") (name "Net-(D203--)") (class "Default")
      (node (ref "D203") (pin "2") (pinfunction "-_2") (pintype "passive"))
      (node (ref "D204") (pin "2") (pinfunction "-_2") (pintype "passive"))
      (node (ref "D205") (pin "2") (pinfunction "-_2") (pintype "passive"))
      (node (ref "R216") (pin "1") (pinfunction "1_1") (pintype "passive"))
      (node (ref "R227") (pin "2") (pinfunction "2_2") (pintype "passive"))
    )
    (net (code "19") (name "Net-(D206--)") (class "Default")
      (node (ref "D206") (pin "2") (pinfunction "-_2") (pintype "passive"))
      (node (ref "Q201") (pin "3") (pinfunction "E_3") (pintype "passive"))
      (node (ref "R228") (pin "2") (pinfunction "2_2") (pintype "passive"))
      (node (ref "T201") (pin "3") (pinfunction "E_3") (pintype "passive"))
    )
    (net (code "20") (name "Net-(D301--)") (class "Default")
      (node (ref "D301") (pin "2") (pinfunction "-_2") (pintype "passive"))
      (node (ref "IC301") (pin "3") (pinfunction "IN_3") (pintype "input"))
    )
    (net (code "21") (name "Net-(D302--)") (class "Default")
      (node (ref "D302") (pin "2") (pinfunction "-_2") (pintype "passive"))
      (node (ref "IC302") (pin "5") (pinfunction "+IN_5") (pintype "input"))
      (node (ref "R304") (pin "2") (pinfunction "2_2") (pintype "passive"))
      (node (ref "R307") (pin "2") (pinfunction "2_2") (pintype "passive"))
    )
    (net (code "22") (name "Net-(DIS101-A)") (class "Default")
      (node (ref "DIS101") (pin "10") (pinfunction "A_10") (pintype "passive"))
      (node (ref "R118") (pin "2") (pinfunction "2_2") (pintype "passive"))
    )
    (net (code "23") (name "Net-(DIS101-B)") (class "Default")
      (node (ref "DIS101") (pin "9") (pinfunction "B_9") (pintype "passive"))
      (node (ref "R119") (pin "2") (pinfunction "2_2") (pintype "passive"))
    )
    (net (code "24") (name "Net-(DIS101-C)") (class "Default")
      (node (ref "DIS101") (pin "8") (pinfunction "C_8") (pintype "passive"))
      (node (ref "R120") (pin "2") (pinfunction "2_2") (pintype "passive"))
    )
    (net (code "25") (name "Net-(DIS101-D)") (class "Default")
      (node (ref "DIS101") (pin "5") (pinfunction "D_5") (pintype "passive"))
      (node (ref "R121") (pin "2") (pinfunction "2_2") (pintype "passive"))
    )
    (net (code "26") (name "Net-(DIS101-E)") (class "Default")
      (node (ref "DIS101") (pin "4") (pinfunction "E_4") (pintype "passive"))
      (node (ref "R122") (pin "2") (pinfunction "2_2") (pintype "passive"))
    )
    (net (code "27") (name "Net-(DIS101-F)") (class "Default")
      (node (ref "DIS101") (pin "2") (pinfunction "F_2") (pintype "passive"))
      (node (ref "R123") (pin "2") (pinfunction "2_2") (pintype "passive"))
    )
    (net (code "28") (name "Net-(DIS101-G)") (class "Default")
      (node (ref "DIS101") (pin "3") (pinfunction "G_3") (pintype "passive"))
      (node (ref "R124") (pin "2") (pinfunction "2_2") (pintype "passive"))
    )
    (net (code "29") (name "Net-(DIS201-A)") (class "Default")
      (node (ref "DIS201") (pin "10") (pinfunction "A_10") (pintype "passive"))
      (node (ref "R218") (pin "2") (pinfunction "2_2") (pintype "passive"))
    )
    (net (code "30") (name "Net-(DIS201-B)") (class "Default")
      (node (ref "DIS201") (pin "9") (pinfunction "B_9") (pintype "passive"))
      (node (ref "R219") (pin "2") (pinfunction "2_2") (pintype "passive"))
    )
    (net (code "31") (name "Net-(DIS201-C)") (class "Default")
      (node (ref "DIS201") (pin "8") (pinfunction "C_8") (pintype "passive"))
      (node (ref "R220") (pin "2") (pinfunction "2_2") (pintype "passive"))
    )
    (net (code "32") (name "Net-(DIS201-D)") (class "Default")
      (node (ref "DIS201") (pin "5") (pinfunction "D_5") (pintype "passive"))
      (node (ref "R221") (pin "2") (pinfunction "2_2") (pintype "passive"))
    )
    (net (code "33") (name "Net-(DIS201-E)") (class "Default")
      (node (ref "DIS201") (pin "4") (pinfunction "E_4") (pintype "passive"))
      (node (ref "R222") (pin "2") (pinfunction "2_2") (pintype "passive"))
    )
    (net (code "34") (name "Net-(DIS201-F)") (class "Default")
      (node (ref "DIS201") (pin "2") (pinfunction "F_2") (pintype "passive"))
      (node (ref "R223") (pin "2") (pinfunction "2_2") (pintype "passive"))
    )
    (net (code "35") (name "Net-(DIS201-G)") (class "Default")
      (node (ref "DIS201") (pin "3") (pinfunction "G_3") (pintype "passive"))
      (node (ref "R224") (pin "2") (pinfunction "2_2") (pintype "passive"))
    )
    (net (code "36") (name "Net-(IC101A--IN)") (class "Default")
      (node (ref "IC101") (pin "4") (pinfunction "-IN_4") (pintype "input"))
      (node (ref "R113") (pin "1") (pinfunction "1_1") (pintype "passive"))
    )
    (net (code "37") (name "Net-(IC101A-OUT)") (class "Default")
      (node (ref "IC101") (pin "13") (pinfunction "OUT_13") (pintype "open_collector"))
      (node (ref "IC101") (pin "2") (pinfunction "OUT_2") (pintype "open_collector"))
      (node (ref "IC102") (pin "4") (pinfunction "BI_4") (pintype "input"))
      (node (ref "R117") (pin "1") (pinfunction "1_1") (pintype "passive"))
    )
    (net (code "38") (name "Net-(IC101B-+IN)") (class "Default")
      (node (ref "IC101") (pin "7") (pinfunction "+IN_7") (pintype "input"))
      (node (ref "R127") (pin "1") (pinfunction "1_1") (pintype "passive"))
    )
    (net (code "39") (name "Net-(IC101B-OUT)") (class "Default")
      (node (ref "IC101") (pin "1") (pinfunction "OUT_1") (pintype "open_collector"))
      (node (ref "R129") (pin "1") (pinfunction "1_1") (pintype "passive"))
    )
    (net (code "40") (name "Net-(IC101C--IN)") (class "Default")
      (node (ref "C101") (pin "1") (pinfunction "1_1") (pintype "passive"))
      (node (ref "IC101") (pin "8") (pinfunction "-IN_8") (pintype "input"))
      (node (ref "R103") (pin "2") (pinfunction "2_2") (pintype "passive"))
      (node (ref "R106") (pin "2") (pinfunction "2_2") (pintype "passive"))
    )
    (net (code "41") (name "Net-(IC101C-OUT)") (class "Default")
      (node (ref "IC101") (pin "14") (pinfunction "OUT_14") (pintype "open_collector"))
      (node (ref "R103") (pin "1") (pinfunction "1_1") (pintype "passive"))
      (node (ref "R104") (pin "1") (pinfunction "1_1") (pintype "passive"))
      (node (ref "R105") (pin "1") (pinfunction "1_1") (pintype "passive"))
    )
    (net (code "42") (name "Net-(IC101D-+IN)") (class "Default")
      (node (ref "IC101") (pin "11") (pinfunction "+IN_11") (pintype "input"))
      (node (ref "R106") (pin "1") (pinfunction "1_1") (pintype "passive"))
    )
    (net (code "43") (name "Net-(IC101D--IN)") (class "Default")
      (node (ref "IC101") (pin "10") (pinfunction "-IN_10") (pintype "input"))
      (node (ref "TM101") (pin "S") (pinfunction "S_S") (pintype "passive"))
    )
    (net (code "44") (name "Net-(IC102A-A)") (class "Default")
      (node (ref "IC102") (pin "13") (pinfunction "A_13") (pintype "output"))
      (node (ref "R118") (pin "1") (pinfunction "1_1") (pintype "passive"))
    )
    (net (code "45") (name "Net-(IC102A-B)") (class "Default")
      (node (ref "IC102") (pin "12") (pinfunction "B_12") (pintype "output"))
      (node (ref "R119") (pin "1") (pinfunction "1_1") (pintype "passive"))
    )
    (net (code "46") (name "Net-(IC102A-C)") (class "Default")
      (node (ref "IC102") (pin "11") (pinfunction "C_11") (pintype "output"))
      (node (ref "R120") (pin "1") (pinfunction "1_1") (pintype "passive"))
    )
    (net (code "47") (name "Net-(IC102A-D)") (class "Default")
      (node (ref "IC102") (pin "10") (pinfunction "D_10") (pintype "output"))
      (node (ref "R121") (pin "1") (pinfunction "1_1") (pintype "passive"))
    )
    (net (code "48") (name "Net-(IC102A-E)") (class "Default")
      (node (ref "IC102") (pin "9") (pinfunction "E_9") (pintype "output"))
      (node (ref "R122") (pin "1") (pinfunction "1_1") (pintype "passive"))
    )
    (net (code "49") (name "Net-(IC102A-F)") (class "Default")
      (node (ref "IC102") (pin "15") (pinfunction "F_15") (pintype "output"))
      (node (ref "R123") (pin "1") (pinfunction "1_1") (pintype "passive"))
    )
    (net (code "50") (name "Net-(IC102A-G)") (class "Default")
      (node (ref "IC102") (pin "14") (pinfunction "G_14") (pintype "output"))
      (node (ref "R124") (pin "1") (pinfunction "1_1") (pintype "passive"))
    )
    (net (code "51") (name "Net-(IC102A-IA)") (class "Default")
      (node (ref "IC102") (pin "7") (pinfunction "IA_7") (pintype "input"))
      (node (ref "R115") (pin "1") (pinfunction "1_1") (pintype "passive"))
    )
    (net (code "52") (name "Net-(IC102A-IB)") (class "Default")
      (node (ref "IC102") (pin "1") (pinfunction "IB_1") (pintype "input"))
      (node (ref "R114") (pin "1") (pinfunction "1_1") (pintype "passive"))
    )
    (net (code "53") (name "Net-(IC102A-IC)") (class "Default")
      (node (ref "IC102") (pin "2") (pinfunction "IC_2") (pintype "input"))
      (node (ref "R112") (pin "1") (pinfunction "1_1") (pintype "passive"))
    )
    (net (code "54") (name "Net-(IC201A--IN)") (class "Default")
      (node (ref "IC201") (pin "4") (pinfunction "-IN_4") (pintype "input"))
      (node (ref "R213") (pin "1") (pinfunction "1_1") (pintype "passive"))
    )
    (net (code "55") (name "Net-(IC201A-OUT)") (class "Default")
      (node (ref "IC201") (pin "13") (pinfunction "OUT_13") (pintype "open_collector"))
      (node (ref "IC201") (pin "2") (pinfunction "OUT_2") (pintype "open_collector"))
      (node (ref "IC202") (pin "4") (pinfunction "BI_4") (pintype "input"))
      (node (ref "R217") (pin "1") (pinfunction "1_1") (pintype "passive"))
    )
    (net (code "56") (name "Net-(IC201B-+IN)") (class "Default")
      (node (ref "IC201") (pin "7") (pinfunction "+IN_7") (pintype "input"))
      (node (ref "R227") (pin "1") (pinfunction "1_1") (pintype "passive"))
    )
    (net (code "57") (name "Net-(IC201B-OUT)") (class "Default")
      (node (ref "IC201") (pin "1") (pinfunction "OUT_1") (pintype "open_collector"))
      (node (ref "R229") (pin "1") (pinfunction "1_1") (pintype "passive"))
    )
    (net (code "58") (name "Net-(IC201C--IN)") (class "Default")
      (node (ref "C201") (pin "1") (pinfunction "1_1") (pintype "passive"))
      (node (ref "IC201") (pin "8") (pinfunction "-IN_8") (pintype "input"))
      (node (ref "R203") (pin "2") (pinfunction "2_2") (pintype "passive"))
      (node (ref "R206") (pin "2") (pinfunction "2_2") (pintype "passive"))
    )
    (net (code "59") (name "Net-(IC201C-OUT)") (class "Default")
      (node (ref "IC201") (pin "14") (pinfunction "OUT_14") (pintype "open_collector"))
      (node (ref "R203") (pin "1") (pinfunction "1_1") (pintype "passive"))
      (node (ref "R204") (pin "1") (pinfunction "1_1") (pintype "passive"))
      (node (ref "R205") (pin "1") (pinfunction "1_1") (pintype "passive"))
    )
    (net (code "60") (name "Net-(IC201D-+IN)") (class "Default")
      (node (ref "IC201") (pin "11") (pinfunction "+IN_11") (pintype "input"))
      (node (ref "R206") (pin "1") (pinfunction "1_1") (pintype "passive"))
    )
    (net (code "61") (name "Net-(IC201D--IN)") (class "Default")
      (node (ref "IC201") (pin "10") (pinfunction "-IN_10") (pintype "input"))
      (node (ref "TM201") (pin "S") (pinfunction "S_S") (pintype "passive"))
    )
    (net (code "62") (name "Net-(IC202A-A)") (class "Default")
      (node (ref "IC202") (pin "13") (pinfunction "A_13") (pintype "output"))
      (node (ref "R218") (pin "1") (pinfunction "1_1") (pintype "passive"))
    )
    (net (code "63") (name "Net-(IC202A-B)") (class "Default")
      (node (ref "IC202") (pin "12") (pinfunction "B_12") (pintype "output"))
      (node (ref "R219") (pin "1") (pinfunction "1_1") (pintype "passive"))
    )
    (net (code "64") (name "Net-(IC202A-C)") (class "Default")
      (node (ref "IC202") (pin "11") (pinfunction "C_11") (pintype "output"))
      (node (ref "R220") (pin "1") (pinfunction "1_1") (pintype "passive"))
    )
    (net (code "65") (name "Net-(IC202A-D)") (class "Default")
      (node (ref "IC202") (pin "10") (pinfunction "D_10") (pintype "output"))
      (node (ref "R221") (pin "1") (pinfunction "1_1") (pintype "passive"))
    )
    (net (code "66") (name "Net-(IC202A-E)") (class "Default")
      (node (ref "IC202") (pin "9") (pinfunction "E_9") (pintype "output"))
      (node (ref "R222") (pin "1") (pinfunction "1_1") (pintype "passive"))
    )
    (net (code "67") (name "Net-(IC202A-F)") (class "Default")
      (node (ref "IC202") (pin "15") (pinfunction "F_15") (pintype "output"))
      (node (ref "R223") (pin "1") (pinfunction "1_1") (pintype "passive"))
    )
    (net (code "68") (name "Net-(IC202A-G)") (class "Default")
      (node (ref "IC202") (pin "14") (pinfunction "G_14") (pintype "output"))
      (node (ref "R224") (pin "1") (pinfunction "1_1") (pintype "passive"))
    )
    (net (code "69") (name "Net-(IC202A-IA)") (class "Default")
      (node (ref "IC202") (pin "7") (pinfunction "IA_7") (pintype "input"))
      (node (ref "R215") (pin "1") (pinfunction "1_1") (pintype "passive"))
    )
    (net (code "70") (name "Net-(IC202A-IB)") (class "Default")
      (node (ref "IC202") (pin "1") (pinfunction "IB_1") (pintype "input"))
      (node (ref "R214") (pin "1") (pinfunction "1_1") (pintype "passive"))
    )
    (net (code "71") (name "Net-(IC202A-IC)") (class "Default")
      (node (ref "IC202") (pin "2") (pinfunction "IC_2") (pintype "input"))
      (node (ref "R212") (pin "1") (pinfunction "1_1") (pintype "passive"))
    )
    (net (code "72") (name "Net-(IC302A-+IN)") (class "Default")
      (node (ref "C301") (pin "1") (pinfunction "1_1") (pintype "passive"))
      (node (ref "IC302") (pin "3") (pinfunction "+IN_3") (pintype "input"))
      (node (ref "R301") (pin "1") (pinfunction "1_1") (pintype "passive"))
    )
    (net (code "73") (name "Net-(IC302A--IN)") (class "Default")
      (node (ref "IC302") (pin "2") (pinfunction "-IN_2") (pintype "input"))
      (node (ref "R302") (pin "2") (pinfunction "2_2") (pintype "passive"))
    )
    (net (code "74") (name "Net-(IC302A-OUT)") (class "Default")
      (node (ref "IC302") (pin "1") (pinfunction "OUT_1") (pintype "output"))
      (node (ref "R303") (pin "2") (pinfunction "2_2") (pintype "passive"))
    )
    (net (code "75") (name "Net-(IC302B--IN)") (class "Default")
      (node (ref "IC302") (pin "6") (pinfunction "-IN_6") (pintype "input"))
      (node (ref "R305") (pin "1") (pinfunction "1_1") (pintype "passive"))
      (node (ref "R306") (pin "2") (pinfunction "2_2") (pintype "passive"))
    )
    (net (code "76") (name "Net-(LEER-P)") (class "Default")
      (node (ref "LEER") (pin "P$1") (pinfunction "P_P$1") (pintype "bidirectional"))
      (node (ref "LEER_") (pin "TP") (pinfunction "PP_TP") (pintype "input"))
      (node (ref "Q101") (pin "2") (pinfunction "C_2") (pintype "passive"))
      (node (ref "T") (pin "2") (pinfunction "C_2") (pintype "passive"))
    )
    (net (code "77") (name "Net-(LEER.-P)") (class "Default")
      (node (ref "LEER.") (pin "P$1") (pinfunction "P_P$1") (pintype "bidirectional"))
      (node (ref "LEER_201") (pin "TP") (pinfunction "PP_TP") (pintype "input"))
      (node (ref "Q201") (pin "2") (pinfunction "C_2") (pintype "passive"))
      (node (ref "T201") (pin "2") (pinfunction "C_2") (pintype "passive"))
    )
    (net (code "78") (name "Net-(PAD1-P)") (class "Default")
      (node (ref "C1") (pin "1") (pinfunction "1_1") (pintype "passive"))
      (node (ref "C10") (pin "2") (pinfunction "2_2") (pintype "passive"))
      (node (ref "C3") (pin "1") (pinfunction "1_1") (pintype "passive"))
      (node (ref "C8") (pin "1") (pinfunction "1_1") (pintype "passive"))
      (node (ref "L1") (pin "1") (pinfunction "1_1") (pintype "passive"))
      (node (ref "PAD1") (pin "1") (pinfunction "P_1") (pintype "passive"))
    )
    (net (code "79") (name "Net-(PAD2-P)") (class "Default")
      (node (ref "C4") (pin "1") (pinfunction "1_1") (pintype "passive"))
      (node (ref "C6") (pin "1") (pinfunction "1_1") (pintype "passive"))
      (node (ref "C8") (pin "2") (pinfunction "2_2") (pintype "passive"))
      (node (ref "C9") (pin "2") (pinfunction "2_2") (pintype "passive"))
      (node (ref "L2") (pin "1") (pinfunction "1_1") (pintype "passive"))
      (node (ref "PAD2") (pin "1") (pinfunction "P_1") (pintype "passive"))
    )
    (net (code "80") (name "Net-(PAD4-P)") (class "Default")
      (node (ref "C10") (pin "1") (pinfunction "1_1") (pintype "passive"))
      (node (ref "C7") (pin "1") (pinfunction "1_1") (pintype "passive"))
      (node (ref "PAD4") (pin "1") (pinfunction "P_1") (pintype "passive"))
    )
    (net (code "81") (name "Net-(PAD5-P)") (class "Default")
      (node (ref "C12") (pin "2") (pinfunction "2_2") (pintype "passive"))
      (node (ref "C13") (pin "1") (pinfunction "1_1") (pintype "passive"))
      (node (ref "PAD5") (pin "1") (pinfunction "P_1") (pintype "passive"))
    )
    (net (code "82") (name "Net-(Q101-B)") (class "Default")
      (node (ref "Q101") (pin "1") (pinfunction "B_1") (pintype "passive"))
      (node (ref "R128") (pin "1") (pinfunction "1_1") (pintype "passive"))
      (node (ref "R129") (pin "2") (pinfunction "2_2") (pintype "passive"))
      (node (ref "T") (pin "1") (pinfunction "B_1") (pintype "passive"))
    )
    (net (code "83") (name "Net-(Q201-B)") (class "Default")
      (node (ref "Q201") (pin "1") (pinfunction "B_1") (pintype "passive"))
      (node (ref "R228") (pin "1") (pinfunction "1_1") (pintype "passive"))
      (node (ref "R229") (pin "2") (pinfunction "2_2") (pintype "passive"))
      (node (ref "T201") (pin "1") (pinfunction "B_1") (pintype "passive"))
    )
    (net (code "84") (name "Net-(R109-Pad1)") (class "Default")
      (node (ref "R109") (pin "1") (pinfunction "1_1") (pintype "passive"))
      (node (ref "TM101") (pin "A") (pinfunction "A_A") (pintype "passive"))
    )
    (net (code "85") (name "Net-(R209-Pad1)") (class "Default")
      (node (ref "R209") (pin "1") (pinfunction "1_1") (pintype "passive"))
      (node (ref "TM201") (pin "A") (pinfunction "A_A") (pintype "passive"))
    )
    (net (code "86") (name "VCC") (class "Default")
      (node (ref "6V") (pin "TP") (pinfunction "PP_TP") (pintype "input"))
      (node (ref "C102") (pin "1") (pinfunction "1_1") (pintype "passive"))
      (node (ref "C203") (pin "1") (pinfunction "1_1") (pintype "passive"))
      (node (ref "C303") (pin "1") (pinfunction "1_1") (pintype "passive"))
      (node (ref "D106") (pin "1") (pinfunction "+_1") (pintype "passive"))
      (node (ref "D107") (pin "C") (pinfunction "C_C") (pintype "passive"))
      (node (ref "D206") (pin "1") (pinfunction "+_1") (pintype "passive"))
      (node (ref "D207") (pin "C") (pinfunction "C_C") (pintype "passive"))
      (node (ref "IC101") (pin "3") (pinfunction "V+_3") (pintype "power_in"))
      (node (ref "IC102") (pin "16") (pinfunction "VDD_16") (pintype "power_in"))
      (node (ref "IC102") (pin "3") (pinfunction "LT_3") (pintype "input"))
      (node (ref "IC201") (pin "3") (pinfunction "V+_3") (pintype "power_in"))
      (node (ref "IC202") (pin "16") (pinfunction "VDD_16") (pintype "power_in"))
      (node (ref "IC202") (pin "3") (pinfunction "LT_3") (pintype "input"))
      (node (ref "IC301") (pin "1") (pinfunction "OUT_1") (pintype "passive"))
      (node (ref "IC302") (pin "8") (pinfunction "V+_8") (pintype "power_in"))
      (node (ref "R101") (pin "2") (pinfunction "2_2") (pintype "passive"))
      (node (ref "R105") (pin "2") (pinfunction "2_2") (pintype "passive"))
      (node (ref "R107") (pin "1") (pinfunction "1_1") (pintype "passive"))
      (node (ref "R108") (pin "1") (pinfunction "1_1") (pintype "passive"))
      (node (ref "R109") (pin "2") (pinfunction "2_2") (pintype "passive"))
      (node (ref "R110") (pin "1") (pinfunction "1_1") (pintype "passive"))
      (node (ref "R111") (pin "1") (pinfunction "1_1") (pintype "passive"))
      (node (ref "R117") (pin "2") (pinfunction "2_2") (pintype "passive"))
      (node (ref "R125") (pin "2") (pinfunction "2_2") (pintype "passive"))
      (node (ref "R130") (pin "2") (pinfunction "2_2") (pintype "passive"))
      (node (ref "R201") (pin "2") (pinfunction "2_2") (pintype "passive"))
      (node (ref "R205") (pin "2") (pinfunction "2_2") (pintype "passive"))
      (node (ref "R207") (pin "1") (pinfunction "1_1") (pintype "passive"))
      (node (ref "R208") (pin "1") (pinfunction "1_1") (pintype "passive"))
      (node (ref "R209") (pin "2") (pinfunction "2_2") (pintype "passive"))
      (node (ref "R210") (pin "1") (pinfunction "1_1") (pintype "passive"))
      (node (ref "R211") (pin "1") (pinfunction "1_1") (pintype "passive"))
      (node (ref "R217") (pin "2") (pinfunction "2_2") (pintype "passive"))
      (node (ref "R225") (pin "2") (pinfunction "2_2") (pintype "passive"))
      (node (ref "R230") (pin "2") (pinfunction "2_2") (pintype "passive"))
      (node (ref "R305") (pin "2") (pinfunction "2_2") (pintype "passive"))
    )
    (net (code "87") (name "VREF_LOGIC") (class "Default")
      (node (ref "IC101") (pin "5") (pinfunction "+IN_5") (pintype "input"))
      (node (ref "IC101") (pin "6") (pinfunction "-IN_6") (pintype "input"))
      (node (ref "IC201") (pin "5") (pinfunction "+IN_5") (pintype "input"))
      (node (ref "IC201") (pin "6") (pinfunction "-IN_6") (pintype "input"))
      (node (ref "R125") (pin "1") (pinfunction "1_1") (pintype "passive"))
      (node (ref "R126") (pin "2") (pinfunction "2_2") (pintype "passive"))
      (node (ref "R225") (pin "1") (pinfunction "1_1") (pintype "passive"))
      (node (ref "R226") (pin "2") (pinfunction "2_2") (pintype "passive"))
    )
    (net (code "88") (name "VREF_OSZ") (class "Default")
      (node (ref "IC101") (pin "9") (pinfunction "+IN_9") (pintype "input"))
      (node (ref "IC201") (pin "9") (pinfunction "+IN_9") (pintype "input"))
      (node (ref "R101") (pin "1") (pinfunction "1_1") (pintype "passive"))
      (node (ref "R102") (pin "2") (pinfunction "2_2") (pintype "passive"))
      (node (ref "R104") (pin "2") (pinfunction "2_2") (pintype "passive"))
      (node (ref "R201") (pin "1") (pinfunction "1_1") (pintype "passive"))
      (node (ref "R202") (pin "2") (pinfunction "2_2") (pintype "passive"))
      (node (ref "R204") (pin "2") (pinfunction "2_2") (pintype "passive"))
    )
    (net (code "89") (name "unconnected-(DIS101-DP-Pad7)") (class "Default")
      (node (ref "DIS101") (pin "7") (pinfunction "DP_7") (pintype "passive"))
    )
    (net (code "90") (name "unconnected-(DIS201-DP-Pad7)") (class "Default")
      (node (ref "DIS201") (pin "7") (pinfunction "DP_7") (pintype "passive"))
    )
    (net (code "91") (name "unconnected-(T-C{slash}-Pad4)") (class "Default")
      (node (ref "T") (pin "4") (pinfunction "C/_4") (pintype "passive"))
    )
    (net (code "92") (name "unconnected-(T201-C{slash}-Pad4)") (class "Default")
      (node (ref "T201") (pin "4") (pinfunction "C/_4") (pintype "passive"))
    )
  )
)
